# Microcontrolador.net
KiCad netlist of a schematic drawn in Altium Designer
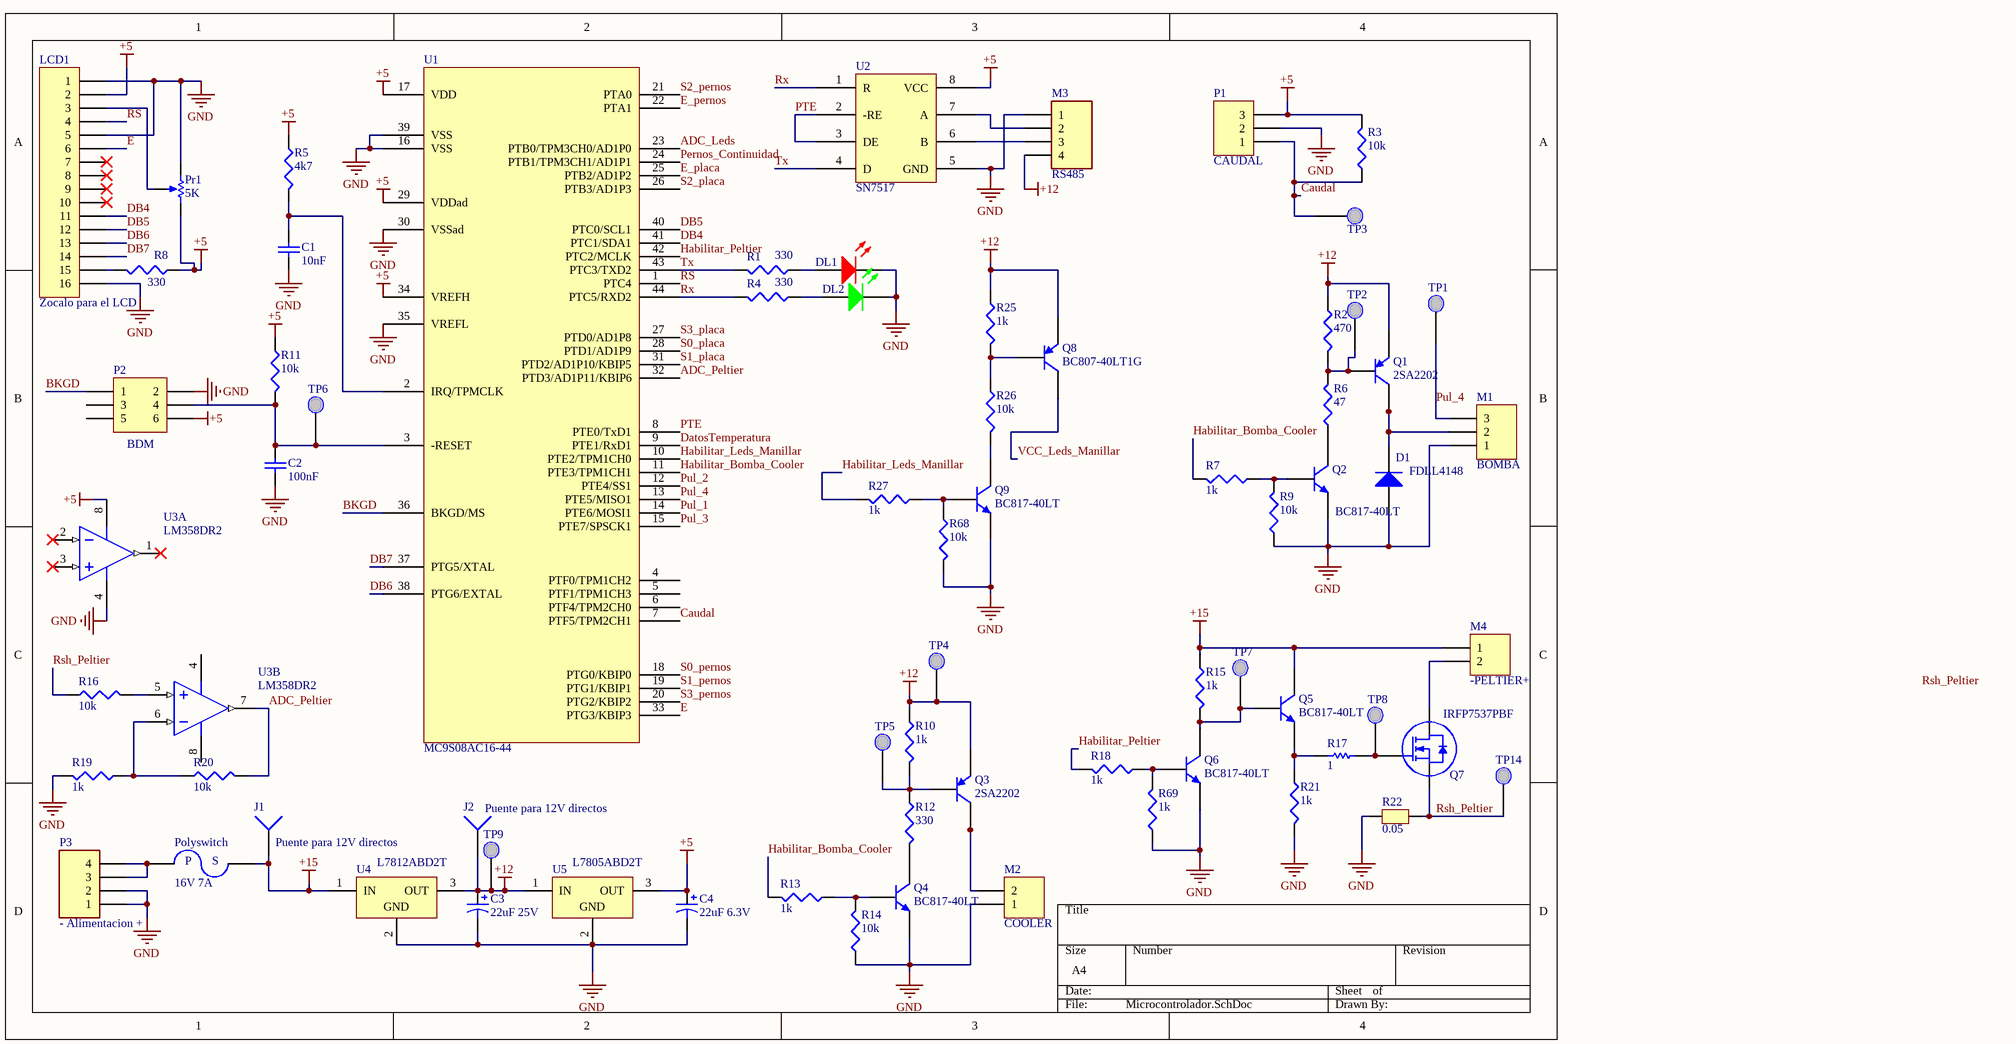
[diagram p0: Microcontrolador.SchDoc]

(export (version "E")
  (design (tool "Eeschema 10.0.6"))
  (components
    (comp (ref "C1")
      (value "10nF")
      (footprint "6-0805_M")
      (description "CAP CER 10000PF 50V 10% X7R 0805")
      (libsource (lib "Miscellaneous Devices") (part "Cap"))
    )
    (comp (ref "C2")
      (value "100nF")
      (footprint "6-0805_M")
      (description "CAP CER 0.1UF 50V 10% X7R 0805")
      (libsource (lib "Miscellaneous Devices") (part "Cap"))
    )
    (comp (ref "C3")
      (value "22uF 25V")
      (footprint "CAP100RP")
      (description "CAP ALUM 22UF 20% 25V RADIAL")
      (fields (field (name "PUBLISHER") "Altium Limited"))
      (libsource (lib "TH_BODY") (part "CAP_ALUM_22UF_25V"))
    )
    (comp (ref "C4")
      (value "22uF 6.3V")
      (footprint "CAP100RP")
      (description "CAP ALUM 22UF 20% 6.3V RADIAL")
      (fields (field (name "PUBLISHER") "Altium Limited"))
      (libsource (lib "TH_BODY") (part "CAP_ALUM_22UF_6.3V"))
    )
    (comp (ref "D1")
      (value "FDLL4148")
      (footprint "SOD-80/MLL34_3D")
      (description "DIODE GEN PURP 100V 200MA LL34/SOD80/MINI MELF")
      (fields (field (name "PUBLISHER") "Altium Limited"))
      (libsource (lib "SMD_BODY") (part "Diode FDLL4148"))
    )
    (comp (ref "DL1")
      (value "Led3mmRojo")
      (footprint "LED-Rojo-3mm")
      (description "LED RED DIFFUSED 3MM ROUND T/H")
      (fields (field (name "PUBLISHER") "Altium Limited"))
      (libsource (lib "TH_Body") (part "Led3mmRojo"))
    )
    (comp (ref "DL2")
      (value "Led3mmVerde")
      (footprint "LED-Verde-3mm")
      (description "LED GREEN DIFFUSED 3MM ROUND T/H")
      (fields (field (name "PUBLISHER") "Altium Limited"))
      (libsource (lib "TH_Body") (part "Led3mmVerde"))
    )
    (comp (ref "J1")
      (value "Puente para 12V directos")
      (footprint "PIN1")
      (fields (field (name "PUBLISHER") "Altium Limited"))
      (libsource (lib "Miscellaneous Connectors") (part "Socket"))
    )
    (comp (ref "J2")
      (value "Puente para 12V directos")
      (footprint "PIN1")
      (fields (field (name "PUBLISHER") "Altium Limited"))
      (libsource (lib "Miscellaneous Connectors") (part "Socket"))
    )
    (comp (ref "LCD1")
      (value "Zocalo para el LCD")
      (footprint "LCD-20x4-Zocalo")
      (description "LCD de 20x4")
      (fields (field (name "PUBLISHER") "Altium Limited"))
      (libsource (lib "Miscellaneous Connectors") (part "Header 16"))
    )
    (comp (ref "M1")
      (value "BOMBA")
      (footprint "AMP100X3")
      (description "CONN HEADER VERT 3POS .100 TIN")
      (fields (field (name "PUBLISHER") "Altium Limited"))
      (libsource (lib "Miscellaneous Connectors") (part "Header 3"))
    )
    (comp (ref "M2")
      (value "COOLER")
      (footprint "640445-2_3D")
      (description "CONN HEADER VERT 2POS .156 TIN")
      (fields (field (name "PUBLISHER") "Altium Limited"))
      (libsource (lib "BODY") (part "640445-2"))
    )
    (comp (ref "M3")
      (value "RS485")
      (footprint "B4B-XH-A_3D")
      (description "CONN HEADER XH TOP 4POS 2.5MM")
      (fields (field (name "PUBLISHER") "Altium Limited"))
      (libsource (lib "") (part "JST_2.5_4_1"))
    )
    (comp (ref "M4")
      (value "-PELTIER+")
      (footprint "640445-2_3D")
      (description "CONN HEADER VERT 2POS .156 TIN")
      (fields (field (name "PUBLISHER") "Altium Limited"))
      (libsource (lib "") (part "640445-2_1"))
    )
    (comp (ref "P1")
      (value "CAUDAL")
      (footprint "B3B-XH-A_3D")
      (description "CONN HEADER XH TOP 3POS 2.5MM")
      (fields (field (name "PUBLISHER") "Altium Limited"))
      (libsource (lib "Connectors_BODY") (part "JST_2.5_3_1"))
    )
    (comp (ref "P2")
      (value "BDM")
      (footprint "HDR2X3_3D")
      (description "DIL VERTICAL PC TAIL PIN HEADER")
      (libsource (lib "Miscellaneous Connectors") (part "Header 3X2"))
    )
    (comp (ref "P3")
      (value "- Alimentacion +")
      (footprint "640445-4_3D")
      (description "CONN HEADER VERT 4POS .156 TIN")
      (fields (field (name "PUBLISHER") "Altium Limited"))
      (libsource (lib "Connectors_BODY") (part "JST_2.5_4"))
    )
    (comp (ref "Polyswitch")
      (value "16V 7A")
      (footprint "Polyswitch 200mils")
      (description "PTC RESET FUSE 16V 7A RADIAL")
      (fields (field (name "PUBLISHER") "*"))
      (libsource (lib "TH_Body") (part "Polyswitch"))
    )
    (comp (ref "Pr1")
      (value "5K")
      (footprint "PRESET V")
      (description "TRIMMER 5K OHM 0.5W PC PIN")
      (fields (field (name "PUBLISHER") "Altium Limited"))
      (libsource (lib "TH_Body") (part "Preset_Multi_Vert_3D"))
    )
    (comp (ref "Q1")
      (value "2SA2202")
      (footprint "sot89_3D")
      (description "TRANS PNP 100V 2A SOT89-3")
      (fields (field (name "PUBLISHER") "Altium Limited"))
      (libsource (lib "SMD_BODY") (part "2SA2202"))
    )
    (comp (ref "Q2")
      (value "BC817-40LT")
      (footprint "SOT23_3D")
      (description "TRANS NPN 45V 0.5A SOT23")
      (fields (field (name "PUBLISHER") "Altium Limited"))
      (libsource (lib "SMD_BODY") (part "BC817"))
    )
    (comp (ref "Q3")
      (value "2SA2202")
      (footprint "sot89_3D")
      (description "TRANS PNP 100V 2A SOT89-3")
      (fields (field (name "PUBLISHER") "Altium Limited"))
      (libsource (lib "SMD_BODY") (part "2SA2202"))
    )
    (comp (ref "Q4")
      (value "BC817-40LT")
      (footprint "SOT23_3D")
      (description "TRANS NPN 45V 0.5A SOT23")
      (fields (field (name "PUBLISHER") "Altium Limited"))
      (libsource (lib "SMD_BODY") (part "BC817"))
    )
    (comp (ref "Q5")
      (value "BC817-40LT")
      (footprint "SOT23_3D")
      (description "TRANS NPN 45V 0.5A SOT23")
      (fields (field (name "PUBLISHER") "Altium Limited"))
      (libsource (lib "SMD_BODY") (part "BC817"))
    )
    (comp (ref "Q6")
      (value "BC817-40LT")
      (footprint "SOT23_3D")
      (description "TRANS NPN 45V 0.5A SOT23")
      (fields (field (name "PUBLISHER") "Altium Limited"))
      (libsource (lib "SMD_BODY") (part "BC817"))
    )
    (comp (ref "Q7")
      (value "IRFP7537PBF")
      (footprint "TO247")
      (description "MOSFET N CH 60V 172A TO247")
      (libsource (lib "LIBEBAL_1108190909") (part "MOSFET N"))
    )
    (comp (ref "Q8")
      (value "BC807-40LT1G")
      (footprint "SOT23_3D")
      (description "TRANS PNP 45V 0.5A SOT23")
      (fields (field (name "PUBLISHER") "Altium Limited"))
      (libsource (lib "SMD_BODY") (part "BC807"))
    )
    (comp (ref "Q9")
      (value "BC817-40LT")
      (footprint "SOT23_3D")
      (description "TRANS NPN 45V 0.5A SOT23")
      (fields (field (name "PUBLISHER") "Altium Limited"))
      (libsource (lib "SMD_BODY") (part "BC817"))
    )
    (comp (ref "R1")
      (value "330")
      (footprint "6-0805_M")
      (description "RES SMD 330 OHM 1% 1/8W 0805")
      (fields (field (name "PUBLISHER") "*"))
      (libsource (lib "Miscellaneous Devices") (part "Res3"))
    )
    (comp (ref "R2")
      (value "470")
      (footprint "6-0805_M")
      (description "RES SMD 470 OHM 1% 1/8W 0805")
      (fields (field (name "PUBLISHER") "*"))
      (libsource (lib "Miscellaneous Devices") (part "Res3"))
    )
    (comp (ref "R3")
      (value "10k")
      (footprint "6-0805_M")
      (description "RES SMD 10K OHM 1% 1/8W 0805")
      (fields (field (name "PUBLISHER") "*"))
      (libsource (lib "Miscellaneous Devices") (part "Res3"))
    )
    (comp (ref "R4")
      (value "330")
      (footprint "6-0805_M")
      (description "RES SMD 330 OHM 1% 1/8W 0805")
      (fields (field (name "PUBLISHER") "*"))
      (libsource (lib "Miscellaneous Devices") (part "Res3"))
    )
    (comp (ref "R5")
      (value "4k7")
      (footprint "6-0805_M")
      (description "RES SMD 4K7 OHM 1% 1/8W 0805")
      (fields (field (name "PUBLISHER") "*"))
      (libsource (lib "Miscellaneous Devices") (part "Res3"))
    )
    (comp (ref "R6")
      (value "47")
      (footprint "6-0805_M")
      (description "RES SMD 47 OHM 5% 1/2W 0805")
      (fields (field (name "PUBLISHER") "*"))
      (libsource (lib "Miscellaneous Devices") (part "Res3"))
    )
    (comp (ref "R7")
      (value "1k")
      (footprint "6-0805_M")
      (description "RES SMD 1K OHM 1% 1/8W 0805")
      (fields (field (name "PUBLISHER") "*"))
      (libsource (lib "Miscellaneous Devices") (part "Res3"))
    )
    (comp (ref "R8")
      (value "330")
      (footprint "6-0805_M")
      (description "RES SMD 330 OHM 1% 1/8W 0805")
      (fields (field (name "PUBLISHER") "*"))
      (libsource (lib "Miscellaneous Devices") (part "Res3"))
    )
    (comp (ref "R9")
      (value "10k")
      (footprint "6-0805_M")
      (description "RES SMD 10K OHM 1% 1/8W 0805")
      (fields (field (name "PUBLISHER") "*"))
      (libsource (lib "Miscellaneous Devices") (part "Res3"))
    )
    (comp (ref "R10")
      (value "1k")
      (footprint "6-0805_M")
      (description "RES SMD 1K OHM 1% 1/8W 0805")
      (fields (field (name "PUBLISHER") "*"))
      (libsource (lib "Miscellaneous Devices") (part "Res3"))
    )
    (comp (ref "R11")
      (value "10k")
      (footprint "6-0805_M")
      (description "RES SMD 10K OHM 1% 1/8W 0805")
      (fields (field (name "PUBLISHER") "*"))
      (libsource (lib "Miscellaneous Devices") (part "Res3"))
    )
    (comp (ref "R12")
      (value "330")
      (footprint "6-0805_M")
      (description "RES SMD 330 OHM 1% 1/8W 0805")
      (fields (field (name "PUBLISHER") "*"))
      (libsource (lib "Miscellaneous Devices") (part "Res3"))
    )
    (comp (ref "R13")
      (value "1k")
      (footprint "6-0805_M")
      (description "RES SMD 1K OHM 1% 1/8W 0805")
      (fields (field (name "PUBLISHER") "*"))
      (libsource (lib "Miscellaneous Devices") (part "Res3"))
    )
    (comp (ref "R14")
      (value "10k")
      (footprint "6-0805_M")
      (description "RES SMD 10K OHM 1% 1/8W 0805")
      (fields (field (name "PUBLISHER") "*"))
      (libsource (lib "Miscellaneous Devices") (part "Res3"))
    )
    (comp (ref "R15")
      (value "1k")
      (footprint "6-0805_M")
      (description "RES SMD 1K OHM 1% 1/8W 0805")
      (fields (field (name "PUBLISHER") "*"))
      (libsource (lib "Miscellaneous Devices") (part "Res3"))
    )
    (comp (ref "R16")
      (value "10k")
      (footprint "6-0805_M")
      (description "RES SMD 10K OHM 1% 1/8W 0805")
      (fields (field (name "PUBLISHER") "*"))
      (libsource (lib "Miscellaneous Devices") (part "Res3"))
    )
    (comp (ref "R17")
      (value "1")
      (footprint "Res-Axial-0.4")
      (description "Resistencia axial de 0.25W y 400 mils")
      (fields (field (name "PUBLISHER") "Altium Limited"))
      (libsource (lib "TH_Body") (part "Resistor-0.25W"))
    )
    (comp (ref "R18")
      (value "1k")
      (footprint "6-0805_M")
      (description "RES SMD 1K OHM 1% 1/8W 0805")
      (fields (field (name "PUBLISHER") "*"))
      (libsource (lib "Miscellaneous Devices") (part "Res3"))
    )
    (comp (ref "R19")
      (value "1k")
      (footprint "6-0805_M")
      (description "RES SMD 1K OHM 1% 1/8W 0805")
      (fields (field (name "PUBLISHER") "*"))
      (libsource (lib "Miscellaneous Devices") (part "Res3"))
    )
    (comp (ref "R20")
      (value "10k")
      (footprint "6-0805_M")
      (description "RES SMD 10K OHM 1% 1/8W 0805")
      (fields (field (name "PUBLISHER") "*"))
      (libsource (lib "Miscellaneous Devices") (part "Res3"))
    )
    (comp (ref "R21")
      (value "1k")
      (footprint "6-0805_M")
      (description "RES SMD 1K OHM 1% 1/8W 0805")
      (fields (field (name "PUBLISHER") "*"))
      (libsource (lib "Miscellaneous Devices") (part "Res3"))
    )
    (comp (ref "R22")
      (value "0.05")
      (footprint "TO-220-Shunt")
      (description "50 mOhms ±5% 35W Through Hole Resistor TO-220-2 Current Sense Thin Film")
      (fields (field (name "PUBLISHER") "Altium Limited"))
      (libsource (lib "TH_BODY") (part "Shunt-0.05Ohms"))
    )
    (comp (ref "R25")
      (value "1k")
      (footprint "6-0805_M")
      (description "RES SMD 1K OHM 1% 1/8W 0805")
      (fields (field (name "PUBLISHER") "*"))
      (libsource (lib "Miscellaneous Devices") (part "Res3"))
    )
    (comp (ref "R26")
      (value "10k")
      (footprint "6-0805_M")
      (description "RES SMD 10K OHM 1% 1/8W 0805")
      (fields (field (name "PUBLISHER") "*"))
      (libsource (lib "Miscellaneous Devices") (part "Res3"))
    )
    (comp (ref "R27")
      (value "1k")
      (footprint "6-0805_M")
      (description "RES SMD 1K OHM 1% 1/8W 0805")
      (fields (field (name "PUBLISHER") "*"))
      (libsource (lib "Miscellaneous Devices") (part "Res3"))
    )
    (comp (ref "R68")
      (value "10k")
      (footprint "6-0805_M")
      (description "RES SMD 10K OHM 1% 1/8W 0805")
      (fields (field (name "PUBLISHER") "*"))
      (libsource (lib "Miscellaneous Devices") (part "Res3"))
    )
    (comp (ref "R69")
      (value "1k")
      (footprint "6-0805_M")
      (description "RES SMD 1K OHM 1% 1/8W 0805")
      (fields (field (name "PUBLISHER") "*"))
      (libsource (lib "Miscellaneous Devices") (part "Res3"))
    )
    (comp (ref "TP1")
      (value "Test point")
      (footprint "TP-5002")
      (fields (field (name "PUBLISHER") "Altium Limited"))
      (libsource (lib "TH_Body") (part "TestPoint"))
    )
    (comp (ref "TP2")
      (value "BaseQ1")
      (footprint "TP-5002")
      (fields (field (name "PUBLISHER") "Altium Limited"))
      (libsource (lib "TH_Body") (part "TestPoint"))
    )
    (comp (ref "TP3")
      (value "Caudal")
      (footprint "TP-5002")
      (fields (field (name "PUBLISHER") "Altium Limited"))
      (libsource (lib "") (part "TestPoint_1"))
    )
    (comp (ref "TP4")
      (value "12v")
      (footprint "TP-5002")
      (fields (field (name "PUBLISHER") "Altium Limited"))
      (libsource (lib "TH_Body") (part "TestPoint"))
    )
    (comp (ref "TP5")
      (value "BaseQ3")
      (footprint "TP-5002")
      (fields (field (name "PUBLISHER") "Altium Limited"))
      (libsource (lib "TH_Body") (part "TestPoint"))
    )
    (comp (ref "TP6")
      (value "Reset")
      (footprint "TP-5002")
      (fields (field (name "PUBLISHER") "Altium Limited"))
      (libsource (lib "TH_Body") (part "TestPoint"))
    )
    (comp (ref "TP7")
      (value "BaseQ5")
      (footprint "TP-5002")
      (fields (field (name "PUBLISHER") "Altium Limited"))
      (libsource (lib "TH_Body") (part "TestPoint"))
    )
    (comp (ref "TP8")
      (value "GateQ7")
      (footprint "TP-5002")
      (fields (field (name "PUBLISHER") "Altium Limited"))
      (libsource (lib "TH_Body") (part "TestPoint"))
    )
    (comp (ref "TP9")
      (value "12v")
      (footprint "TP-5002")
      (fields (field (name "PUBLISHER") "Altium Limited"))
      (libsource (lib "TH_Body") (part "TestPoint"))
    )
    (comp (ref "TP14")
      (value "Vshunt")
      (footprint "TP-5002")
      (fields (field (name "PUBLISHER") "Altium Limited"))
      (libsource (lib "TH_Body") (part "TestPoint"))
    )
    (comp (ref "U1")
      (value "MC9S08AC16-44")
      (footprint "QFP10x10-G44/Z14.4N_3D")
      (description "S08 S08 Microcontroller IC 8-Bit 40MHz 16KB (16K x 8) FLASH 32-LQFP (7x7)")
      (fields (field (name "PUBLISHER") "*"))
      (libsource (lib "TH_Body") (part "SMD-MC9S08AC16-44"))
    )
    (comp (ref "U2")
      (value "SN7517")
      (footprint "751-07_N")
      (description "IC TXRX DIFF BUSS 8SOIC")
      (fields (field (name "PUBLISHER") "Altium Limited"))
      (libsource (lib "SMD_BODY") (part "SN7517"))
    )
    (comp (ref "U3")
      (value "LM358DR2")
      (footprint "751-07_L")
      (description "Single-Supply Dual Operational Amplifier")
      (fields (field (name "PUBLISHER") "Altium Limited"))
      (libsource (lib "SMD_BODY") (part "LM358DR2"))
    )
    (comp (ref "U4")
      (value "L7812ABD2T")
      (footprint "TO-263")
      (description "IC REG LINEAR 12V 1.5A D2PAK")
      (fields (field (name "PUBLISHER") "Altium Limited"))
      (libsource (lib "SMD_BODY") (part "L7805ABD2T"))
    )
    (comp (ref "U5")
      (value "L7805ABD2T")
      (footprint "TO-263")
      (description "IC REG LINEAR 5V 1.5A D2PAK")
      (fields (field (name "PUBLISHER") "Altium Limited"))
      (libsource (lib "SMD_BODY") (part "L7805ABD2T"))
    )
  )
  (nets
    (net (code "1") (name "+5") (class "Default")
      (node (ref "C4") (pin "1") (pinfunction "1_1") (pintype "passive"))
      (node (ref "LCD1") (pin "2") (pinfunction "2_2") (pintype "passive"))
      (node (ref "P1") (pin "3") (pinfunction "3_3") (pintype "passive"))
      (node (ref "P2") (pin "6") (pinfunction "6_6") (pintype "passive"))
      (node (ref "Pr1") (pin "3") (pinfunction "BOT_CW_3") (pintype "passive"))
      (node (ref "R11") (pin "1") (pinfunction "1_1") (pintype "passive"))
      (node (ref "R3") (pin "2") (pinfunction "2_2") (pintype "passive"))
      (node (ref "R5") (pin "1") (pinfunction "1_1") (pintype "passive"))
      (node (ref "R8") (pin "1") (pinfunction "1_1") (pintype "passive"))
      (node (ref "U1") (pin "17") (pinfunction "VDD_17") (pintype "passive"))
      (node (ref "U1") (pin "29") (pinfunction "VDDad_29") (pintype "passive"))
      (node (ref "U1") (pin "34") (pinfunction "VREFH_34") (pintype "passive"))
      (node (ref "U2") (pin "8") (pinfunction "VCC_8") (pintype "passive"))
      (node (ref "U3") (pin "8") (pinfunction "V+_8") (pintype "power_in"))
      (node (ref "U5") (pin "3") (pinfunction "OUT_3") (pintype "power_in"))
    )
    (net (code "2") (name "+12") (class "Default")
      (node (ref "C3") (pin "1") (pinfunction "1_1") (pintype "passive"))
      (node (ref "J2") (pin "1") (pinfunction "1_1") (pintype "passive"))
      (node (ref "M3") (pin "4") (pinfunction "4_4") (pintype "passive"))
      (node (ref "Q1") (pin "3") (pinfunction "E_3") (pintype "passive"))
      (node (ref "Q3") (pin "3") (pinfunction "E_3") (pintype "passive"))
      (node (ref "Q8") (pin "2") (pinfunction "E_2") (pintype "passive"))
      (node (ref "R10") (pin "1") (pinfunction "1_1") (pintype "passive"))
      (node (ref "R2") (pin "1") (pinfunction "1_1") (pintype "passive"))
      (node (ref "R25") (pin "1") (pinfunction "1_1") (pintype "passive"))
      (node (ref "TP4") (pin "1") (pinfunction "1_1") (pintype "passive"))
      (node (ref "TP9") (pin "1") (pinfunction "1_1") (pintype "passive"))
      (node (ref "U4") (pin "3") (pinfunction "OUT_3") (pintype "power_in"))
      (node (ref "U5") (pin "1") (pinfunction "IN_1") (pintype "power_in"))
    )
    (net (code "3") (name "+15") (class "Default")
      (node (ref "J1") (pin "1") (pinfunction "1_1") (pintype "passive"))
      (node (ref "M4") (pin "1") (pinfunction "1_1") (pintype "passive"))
      (node (ref "Polyswitch") (pin "1") (pinfunction "1_1") (pintype "passive"))
      (node (ref "Q5") (pin "3") (pinfunction "C_3") (pintype "passive"))
      (node (ref "R15") (pin "1") (pinfunction "1_1") (pintype "passive"))
      (node (ref "U4") (pin "1") (pinfunction "IN_1") (pintype "power_in"))
    )
    (net (code "4") (name "/ADC_Leds") (class "Default")
      (node (ref "U1") (pin "23") (pinfunction "PTB0/TPM3CH0/AD1P0_23") (pintype "passive"))
    )
    (net (code "5") (name "/ADC_Peltier") (class "Default")
      (node (ref "R20") (pin "2") (pinfunction "2_2") (pintype "passive"))
      (node (ref "U1") (pin "32") (pinfunction "PTD3/AD1P11/KBIP6_32") (pintype "passive"))
      (node (ref "U3") (pin "7") (pinfunction "OUT_7") (pintype "output"))
    )
    (net (code "6") (name "/BKGD") (class "Default")
      (node (ref "P2") (pin "1") (pinfunction "1_1") (pintype "passive"))
      (node (ref "U1") (pin "36") (pinfunction "BKGD/MS_36") (pintype "passive"))
    )
    (net (code "7") (name "/Caudal") (class "Default")
      (node (ref "P1") (pin "1") (pinfunction "1_1") (pintype "passive"))
      (node (ref "R3") (pin "1") (pinfunction "1_1") (pintype "passive"))
      (node (ref "TP3") (pin "1") (pinfunction "1_1") (pintype "passive"))
      (node (ref "U1") (pin "7") (pinfunction "PTF5/TPM2CH1_7") (pintype "passive"))
    )
    (net (code "8") (name "/DB4") (class "Default")
      (node (ref "LCD1") (pin "11") (pinfunction "11_11") (pintype "passive"))
      (node (ref "U1") (pin "41") (pinfunction "PTC1/SDA1_41") (pintype "passive"))
    )
    (net (code "9") (name "/DB5") (class "Default")
      (node (ref "LCD1") (pin "12") (pinfunction "12_12") (pintype "passive"))
      (node (ref "U1") (pin "40") (pinfunction "PTC0/SCL1_40") (pintype "passive"))
    )
    (net (code "10") (name "/DB6") (class "Default")
      (node (ref "LCD1") (pin "13") (pinfunction "13_13") (pintype "passive"))
      (node (ref "U1") (pin "38") (pinfunction "PTG6/EXTAL_38") (pintype "passive"))
    )
    (net (code "11") (name "/DB7") (class "Default")
      (node (ref "LCD1") (pin "14") (pinfunction "14_14") (pintype "passive"))
      (node (ref "U1") (pin "37") (pinfunction "PTG5/XTAL_37") (pintype "passive"))
    )
    (net (code "12") (name "/DatosTemperatura") (class "Default")
      (node (ref "U1") (pin "9") (pinfunction "PTE1/RxD1_9") (pintype "passive"))
    )
    (net (code "13") (name "/E") (class "Default")
      (node (ref "LCD1") (pin "6") (pinfunction "6_6") (pintype "passive"))
      (node (ref "U1") (pin "33") (pinfunction "PTG3/KBIP3_33") (pintype "passive"))
    )
    (net (code "14") (name "/E_pernos") (class "Default")
      (node (ref "U1") (pin "22") (pinfunction "PTA1_22") (pintype "passive"))
    )
    (net (code "15") (name "/E_placa") (class "Default")
      (node (ref "U1") (pin "25") (pinfunction "PTB2/AD1P2_25") (pintype "passive"))
    )
    (net (code "16") (name "/Habilitar_Bomba_Cooler") (class "Default")
      (node (ref "R13") (pin "2") (pinfunction "2_2") (pintype "passive"))
      (node (ref "R7") (pin "2") (pinfunction "2_2") (pintype "passive"))
      (node (ref "U1") (pin "11") (pinfunction "PTE3/TPM1CH1_11") (pintype "passive"))
    )
    (net (code "17") (name "/Habilitar_Leds_Manillar") (class "Default")
      (node (ref "R27") (pin "2") (pinfunction "2_2") (pintype "passive"))
      (node (ref "U1") (pin "10") (pinfunction "PTE2/TPM1CH0_10") (pintype "passive"))
    )
    (net (code "18") (name "/Habilitar_Peltier") (class "Default")
      (node (ref "R18") (pin "2") (pinfunction "2_2") (pintype "passive"))
      (node (ref "U1") (pin "42") (pinfunction "PTC2/MCLK_42") (pintype "passive"))
    )
    (net (code "19") (name "/PTE") (class "Default")
      (node (ref "U1") (pin "8") (pinfunction "PTE0/TxD1_8") (pintype "passive"))
      (node (ref "U2") (pin "2") (pinfunction "-RE_2") (pintype "passive"))
      (node (ref "U2") (pin "3") (pinfunction "DE_3") (pintype "passive"))
    )
    (net (code "20") (name "/Pernos_Continuidad") (class "Default")
      (node (ref "U1") (pin "24") (pinfunction "PTB1/TPM3CH1/AD1P1_24") (pintype "passive"))
    )
    (net (code "21") (name "/Pul_1") (class "Default")
      (node (ref "U1") (pin "14") (pinfunction "PTE6/MOSI1_14") (pintype "passive"))
    )
    (net (code "22") (name "/Pul_2") (class "Default")
      (node (ref "U1") (pin "12") (pinfunction "PTE4/SS1_12") (pintype "passive"))
    )
    (net (code "23") (name "/Pul_3") (class "Default")
      (node (ref "U1") (pin "15") (pinfunction "PTE7/SPSCK1_15") (pintype "passive"))
    )
    (net (code "24") (name "/Pul_4") (class "Default")
      (node (ref "M1") (pin "3") (pinfunction "3_3") (pintype "passive"))
      (node (ref "TP1") (pin "1") (pinfunction "1_1") (pintype "passive"))
      (node (ref "U1") (pin "13") (pinfunction "PTE5/MISO1_13") (pintype "passive"))
    )
    (net (code "25") (name "/RS") (class "Default")
      (node (ref "LCD1") (pin "4") (pinfunction "4_4") (pintype "passive"))
      (node (ref "U1") (pin "1") (pinfunction "PTC4_1") (pintype "passive"))
    )
    (net (code "26") (name "/Rsh_Peltier") (class "Default")
      (node (ref "Q7") (pin "3") (pinfunction "S_3") (pintype "passive"))
      (node (ref "R16") (pin "1") (pinfunction "1_1") (pintype "passive"))
      (node (ref "R22") (pin "3") (pinfunction "3_3") (pintype "passive"))
      (node (ref "TP14") (pin "1") (pinfunction "1_1") (pintype "passive"))
    )
    (net (code "27") (name "/Rx") (class "Default")
      (node (ref "R4") (pin "2") (pinfunction "2_2") (pintype "passive"))
      (node (ref "U1") (pin "44") (pinfunction "PTC5/RXD2_44") (pintype "passive"))
      (node (ref "U2") (pin "1") (pinfunction "R_1") (pintype "passive"))
    )
    (net (code "28") (name "/S0_pernos") (class "Default")
      (node (ref "U1") (pin "18") (pinfunction "PTG0/KBIP0_18") (pintype "passive"))
    )
    (net (code "29") (name "/S0_placa") (class "Default")
      (node (ref "U1") (pin "28") (pinfunction "PTD1/AD1P9_28") (pintype "passive"))
    )
    (net (code "30") (name "/S1_pernos") (class "Default")
      (node (ref "U1") (pin "19") (pinfunction "PTG1/KBIP1_19") (pintype "passive"))
    )
    (net (code "31") (name "/S1_placa") (class "Default")
      (node (ref "U1") (pin "31") (pinfunction "PTD2/AD1P10/KBIP5_31") (pintype "passive"))
    )
    (net (code "32") (name "/S2_pernos") (class "Default")
      (node (ref "U1") (pin "21") (pinfunction "PTA0_21") (pintype "passive"))
    )
    (net (code "33") (name "/S2_placa") (class "Default")
      (node (ref "U1") (pin "26") (pinfunction "PTB3/AD1P3_26") (pintype "passive"))
    )
    (net (code "34") (name "/S3_pernos") (class "Default")
      (node (ref "U1") (pin "20") (pinfunction "PTG2/KBIP2_20") (pintype "passive"))
    )
    (net (code "35") (name "/S3_placa") (class "Default")
      (node (ref "U1") (pin "27") (pinfunction "PTD0/AD1P8_27") (pintype "passive"))
    )
    (net (code "36") (name "/Tx") (class "Default")
      (node (ref "R1") (pin "2") (pinfunction "2_2") (pintype "passive"))
      (node (ref "U1") (pin "43") (pinfunction "PTC3/TXD2_43") (pintype "passive"))
      (node (ref "U2") (pin "4") (pinfunction "D_4") (pintype "passive"))
    )
    (net (code "37") (name "/VCC_Leds_Manillar") (class "Default")
      (node (ref "Q8") (pin "3") (pinfunction "C_3") (pintype "passive"))
    )
    (net (code "38") (name "GND") (class "Default")
      (node (ref "C1") (pin "1") (pinfunction "1_1") (pintype "passive"))
      (node (ref "C2") (pin "1") (pinfunction "1_1") (pintype "passive"))
      (node (ref "C3") (pin "2") (pinfunction "2_2") (pintype "passive"))
      (node (ref "C4") (pin "2") (pinfunction "2_2") (pintype "passive"))
      (node (ref "D1") (pin "1") (pinfunction "A_1") (pintype "passive"))
      (node (ref "DL1") (pin "2") (pinfunction "K_2") (pintype "passive"))
      (node (ref "DL2") (pin "2") (pinfunction "K_2") (pintype "passive"))
      (node (ref "LCD1") (pin "1") (pinfunction "1_1") (pintype "passive"))
      (node (ref "LCD1") (pin "16") (pinfunction "16_16") (pintype "passive"))
      (node (ref "LCD1") (pin "5") (pinfunction "5_5") (pintype "passive"))
      (node (ref "M1") (pin "1") (pinfunction "1_1") (pintype "passive"))
      (node (ref "M2") (pin "1") (pinfunction "1_1") (pintype "passive"))
      (node (ref "M3") (pin "1") (pinfunction "1_1") (pintype "passive"))
      (node (ref "P1") (pin "2") (pinfunction "2_2") (pintype "passive"))
      (node (ref "P2") (pin "2") (pinfunction "2_2") (pintype "passive"))
      (node (ref "P3") (pin "1") (pinfunction "1_1") (pintype "passive"))
      (node (ref "P3") (pin "2") (pinfunction "2_2") (pintype "passive"))
      (node (ref "Pr1") (pin "1") (pinfunction "TOP_CCW_1") (pintype "passive"))
      (node (ref "Q2") (pin "2") (pinfunction "E_2") (pintype "passive"))
      (node (ref "Q4") (pin "2") (pinfunction "E_2") (pintype "passive"))
      (node (ref "Q6") (pin "2") (pinfunction "E_2") (pintype "passive"))
      (node (ref "Q9") (pin "2") (pinfunction "E_2") (pintype "passive"))
      (node (ref "R14") (pin "1") (pinfunction "1_1") (pintype "passive"))
      (node (ref "R19") (pin "2") (pinfunction "2_2") (pintype "passive"))
      (node (ref "R21") (pin "2") (pinfunction "2_2") (pintype "passive"))
      (node (ref "R22") (pin "1") (pinfunction "1_1") (pintype "passive"))
      (node (ref "R68") (pin "2") (pinfunction "2_2") (pintype "passive"))
      (node (ref "R69") (pin "1") (pinfunction "1_1") (pintype "passive"))
      (node (ref "R9") (pin "1") (pinfunction "1_1") (pintype "passive"))
      (node (ref "U1") (pin "16") (pinfunction "VSS_16") (pintype "passive"))
      (node (ref "U1") (pin "30") (pinfunction "VSSad_30") (pintype "passive"))
      (node (ref "U1") (pin "35") (pinfunction "VREFL_35") (pintype "passive"))
      (node (ref "U1") (pin "39") (pinfunction "VSS_39") (pintype "passive"))
      (node (ref "U2") (pin "5") (pinfunction "GND_5") (pintype "passive"))
      (node (ref "U3") (pin "4") (pinfunction "V-_4") (pintype "power_in"))
      (node (ref "U4") (pin "2") (pinfunction "GND_2") (pintype "power_in"))
      (node (ref "U5") (pin "2") (pinfunction "GND_2") (pintype "power_in"))
    )
    (net (code "39") (name "Net-(D1-K)") (class "Default")
      (node (ref "D1") (pin "2") (pinfunction "K_2") (pintype "passive"))
      (node (ref "M1") (pin "2") (pinfunction "2_2") (pintype "passive"))
      (node (ref "Q1") (pin "0") (pinfunction "C_0") (pintype "passive"))
      (node (ref "Q1") (pin "2") (pinfunction "C_2") (pintype "passive"))
    )
    (net (code "40") (name "Net-(DL1-A)") (class "Default")
      (node (ref "DL1") (pin "1") (pinfunction "A_1") (pintype "passive"))
      (node (ref "R1") (pin "1") (pinfunction "1_1") (pintype "passive"))
    )
    (net (code "41") (name "Net-(DL2-A)") (class "Default")
      (node (ref "DL2") (pin "1") (pinfunction "A_1") (pintype "passive"))
      (node (ref "R4") (pin "1") (pinfunction "1_1") (pintype "passive"))
    )
    (net (code "42") (name "Net-(LCD1-Pad15)") (class "Default")
      (node (ref "LCD1") (pin "15") (pinfunction "15_15") (pintype "passive"))
      (node (ref "R8") (pin "2") (pinfunction "2_2") (pintype "passive"))
    )
    (net (code "43") (name "Net-(M2-Pad2)") (class "Default")
      (node (ref "M2") (pin "2") (pinfunction "2_2") (pintype "passive"))
      (node (ref "Q3") (pin "0") (pinfunction "C_0") (pintype "passive"))
      (node (ref "Q3") (pin "2") (pinfunction "C_2") (pintype "passive"))
    )
    (net (code "44") (name "Net-(P3-Pad3)") (class "Default")
      (node (ref "P3") (pin "3") (pinfunction "3_3") (pintype "passive"))
      (node (ref "P3") (pin "4") (pinfunction "4_4") (pintype "passive"))
      (node (ref "Polyswitch") (pin "2") (pinfunction "2_2") (pintype "passive"))
    )
    (net (code "45") (name "Net-(Pr1-TAP)") (class "Default")
      (node (ref "LCD1") (pin "3") (pinfunction "3_3") (pintype "passive"))
      (node (ref "Pr1") (pin "2") (pinfunction "TAP_2") (pintype "passive"))
    )
    (net (code "46") (name "Net-(Q1-B)") (class "Default")
      (node (ref "Q1") (pin "1") (pinfunction "B_1") (pintype "passive"))
      (node (ref "R2") (pin "2") (pinfunction "2_2") (pintype "passive"))
      (node (ref "R6") (pin "2") (pinfunction "2_2") (pintype "passive"))
      (node (ref "TP2") (pin "1") (pinfunction "1_1") (pintype "passive"))
    )
    (net (code "47") (name "Net-(Q2-B)") (class "Default")
      (node (ref "Q2") (pin "1") (pinfunction "B_1") (pintype "passive"))
      (node (ref "R7") (pin "1") (pinfunction "1_1") (pintype "passive"))
      (node (ref "R9") (pin "2") (pinfunction "2_2") (pintype "passive"))
    )
    (net (code "48") (name "Net-(Q2-C)") (class "Default")
      (node (ref "Q2") (pin "3") (pinfunction "C_3") (pintype "passive"))
      (node (ref "R6") (pin "1") (pinfunction "1_1") (pintype "passive"))
    )
    (net (code "49") (name "Net-(Q3-B)") (class "Default")
      (node (ref "Q3") (pin "1") (pinfunction "B_1") (pintype "passive"))
      (node (ref "R10") (pin "2") (pinfunction "2_2") (pintype "passive"))
      (node (ref "R12") (pin "1") (pinfunction "1_1") (pintype "passive"))
      (node (ref "TP5") (pin "1") (pinfunction "1_1") (pintype "passive"))
    )
    (net (code "50") (name "Net-(Q4-B)") (class "Default")
      (node (ref "Q4") (pin "1") (pinfunction "B_1") (pintype "passive"))
      (node (ref "R13") (pin "1") (pinfunction "1_1") (pintype "passive"))
      (node (ref "R14") (pin "2") (pinfunction "2_2") (pintype "passive"))
    )
    (net (code "51") (name "Net-(Q4-C)") (class "Default")
      (node (ref "Q4") (pin "3") (pinfunction "C_3") (pintype "passive"))
      (node (ref "R12") (pin "2") (pinfunction "2_2") (pintype "passive"))
    )
    (net (code "52") (name "Net-(Q5-B)") (class "Default")
      (node (ref "Q5") (pin "1") (pinfunction "B_1") (pintype "passive"))
      (node (ref "Q6") (pin "3") (pinfunction "C_3") (pintype "passive"))
      (node (ref "R15") (pin "2") (pinfunction "2_2") (pintype "passive"))
      (node (ref "TP7") (pin "1") (pinfunction "1_1") (pintype "passive"))
    )
    (net (code "53") (name "Net-(Q5-E)") (class "Default")
      (node (ref "Q5") (pin "2") (pinfunction "E_2") (pintype "passive"))
      (node (ref "R17") (pin "2") (pinfunction "2_2") (pintype "passive"))
      (node (ref "R21") (pin "1") (pinfunction "1_1") (pintype "passive"))
    )
    (net (code "54") (name "Net-(Q6-B)") (class "Default")
      (node (ref "Q6") (pin "1") (pinfunction "B_1") (pintype "passive"))
      (node (ref "R18") (pin "1") (pinfunction "1_1") (pintype "passive"))
      (node (ref "R69") (pin "2") (pinfunction "2_2") (pintype "passive"))
    )
    (net (code "55") (name "Net-(Q7-D)") (class "Default")
      (node (ref "M4") (pin "2") (pinfunction "2_2") (pintype "passive"))
      (node (ref "Q7") (pin "2") (pinfunction "D_2") (pintype "passive"))
    )
    (net (code "56") (name "Net-(Q7-G)") (class "Default")
      (node (ref "Q7") (pin "1") (pinfunction "G_1") (pintype "passive"))
      (node (ref "R17") (pin "1") (pinfunction "1_1") (pintype "passive"))
      (node (ref "TP8") (pin "1") (pinfunction "1_1") (pintype "passive"))
    )
    (net (code "57") (name "Net-(Q8-B)") (class "Default")
      (node (ref "Q8") (pin "1") (pinfunction "B_1") (pintype "passive"))
      (node (ref "R25") (pin "2") (pinfunction "2_2") (pintype "passive"))
      (node (ref "R26") (pin "1") (pinfunction "1_1") (pintype "passive"))
    )
    (net (code "58") (name "Net-(Q9-B)") (class "Default")
      (node (ref "Q9") (pin "1") (pinfunction "B_1") (pintype "passive"))
      (node (ref "R27") (pin "1") (pinfunction "1_1") (pintype "passive"))
      (node (ref "R68") (pin "1") (pinfunction "1_1") (pintype "passive"))
    )
    (net (code "59") (name "Net-(Q9-C)") (class "Default")
      (node (ref "Q9") (pin "3") (pinfunction "C_3") (pintype "passive"))
      (node (ref "R26") (pin "2") (pinfunction "2_2") (pintype "passive"))
    )
    (net (code "60") (name "Net-(U1--RESET)") (class "Default")
      (node (ref "C2") (pin "2") (pinfunction "2_2") (pintype "passive"))
      (node (ref "P2") (pin "4") (pinfunction "4_4") (pintype "passive"))
      (node (ref "R11") (pin "2") (pinfunction "2_2") (pintype "passive"))
      (node (ref "TP6") (pin "1") (pinfunction "1_1") (pintype "passive"))
      (node (ref "U1") (pin "3") (pinfunction "-RESET_3") (pintype "passive"))
    )
    (net (code "61") (name "Net-(U1-IRQ{slash}TPMCLK)") (class "Default")
      (node (ref "C1") (pin "2") (pinfunction "2_2") (pintype "passive"))
      (node (ref "R5") (pin "2") (pinfunction "2_2") (pintype "passive"))
      (node (ref "U1") (pin "2") (pinfunction "IRQ/TPMCLK_2") (pintype "passive"))
    )
    (net (code "62") (name "Net-(U2-A)") (class "Default")
      (node (ref "M3") (pin "2") (pinfunction "2_2") (pintype "passive"))
      (node (ref "U2") (pin "7") (pinfunction "A_7") (pintype "passive"))
    )
    (net (code "63") (name "Net-(U2-B)") (class "Default")
      (node (ref "M3") (pin "3") (pinfunction "3_3") (pintype "passive"))
      (node (ref "U2") (pin "6") (pinfunction "B_6") (pintype "passive"))
    )
    (net (code "64") (name "Net-(U3B-IN+)") (class "Default")
      (node (ref "R16") (pin "2") (pinfunction "2_2") (pintype "passive"))
      (node (ref "U3") (pin "5") (pinfunction "IN+_5") (pintype "input"))
    )
    (net (code "65") (name "Net-(U3B-IN-)") (class "Default")
      (node (ref "R19") (pin "1") (pinfunction "1_1") (pintype "passive"))
      (node (ref "R20") (pin "1") (pinfunction "1_1") (pintype "passive"))
      (node (ref "U3") (pin "6") (pinfunction "IN-_6") (pintype "input"))
    )
    (net (code "66") (name "unconnected-(LCD1-Pad7)") (class "Default")
      (node (ref "LCD1") (pin "7") (pinfunction "7_7") (pintype "passive+no_connect"))
    )
    (net (code "67") (name "unconnected-(LCD1-Pad8)") (class "Default")
      (node (ref "LCD1") (pin "8") (pinfunction "8_8") (pintype "passive+no_connect"))
    )
    (net (code "68") (name "unconnected-(LCD1-Pad9)") (class "Default")
      (node (ref "LCD1") (pin "9") (pinfunction "9_9") (pintype "passive+no_connect"))
    )
    (net (code "69") (name "unconnected-(LCD1-Pad10)") (class "Default")
      (node (ref "LCD1") (pin "10") (pinfunction "10_10") (pintype "passive+no_connect"))
    )
    (net (code "70") (name "unconnected-(P2-Pad3)") (class "Default")
      (node (ref "P2") (pin "3") (pinfunction "3_3") (pintype "passive"))
    )
    (net (code "71") (name "unconnected-(P2-Pad5)") (class "Default")
      (node (ref "P2") (pin "5") (pinfunction "5_5") (pintype "passive"))
    )
    (net (code "72") (name "unconnected-(U1-PTF0{slash}TPM1CH2-Pad4)") (class "Default")
      (node (ref "U1") (pin "4") (pinfunction "PTF0/TPM1CH2_4") (pintype "passive"))
    )
    (net (code "73") (name "unconnected-(U1-PTF1{slash}TPM1CH3-Pad5)") (class "Default")
      (node (ref "U1") (pin "5") (pinfunction "PTF1/TPM1CH3_5") (pintype "passive"))
    )
    (net (code "74") (name "unconnected-(U1-PTF4{slash}TPM2CH0-Pad6)") (class "Default")
      (node (ref "U1") (pin "6") (pinfunction "PTF4/TPM2CH0_6") (pintype "passive"))
    )
    (net (code "75") (name "unconnected-(U3A-IN+-Pad3)") (class "Default")
      (node (ref "U3") (pin "3") (pinfunction "IN+_3") (pintype "input+no_connect"))
    )
    (net (code "76") (name "unconnected-(U3A-IN--Pad2)") (class "Default")
      (node (ref "U3") (pin "2") (pinfunction "IN-_2") (pintype "input+no_connect"))
    )
    (net (code "77") (name "unconnected-(U3A-OUT-Pad1)") (class "Default")
      (node (ref "U3") (pin "1") (pinfunction "OUT_1") (pintype "output+no_connect"))
    )
    (net (code "78") (name "unconnected-(U3B-V+-Pad8)") (class "Default")
      (node (ref "U3") (pin "8") (pinfunction "V+_8") (pintype "power_in"))
    )
    (net (code "79") (name "unconnected-(U3B-V--Pad4)") (class "Default")
      (node (ref "U3") (pin "4") (pinfunction "V-_4") (pintype "power_in"))
    )
  )
)
